# TSAL.net
KiCad netlist of a schematic drawn in Altium Designer
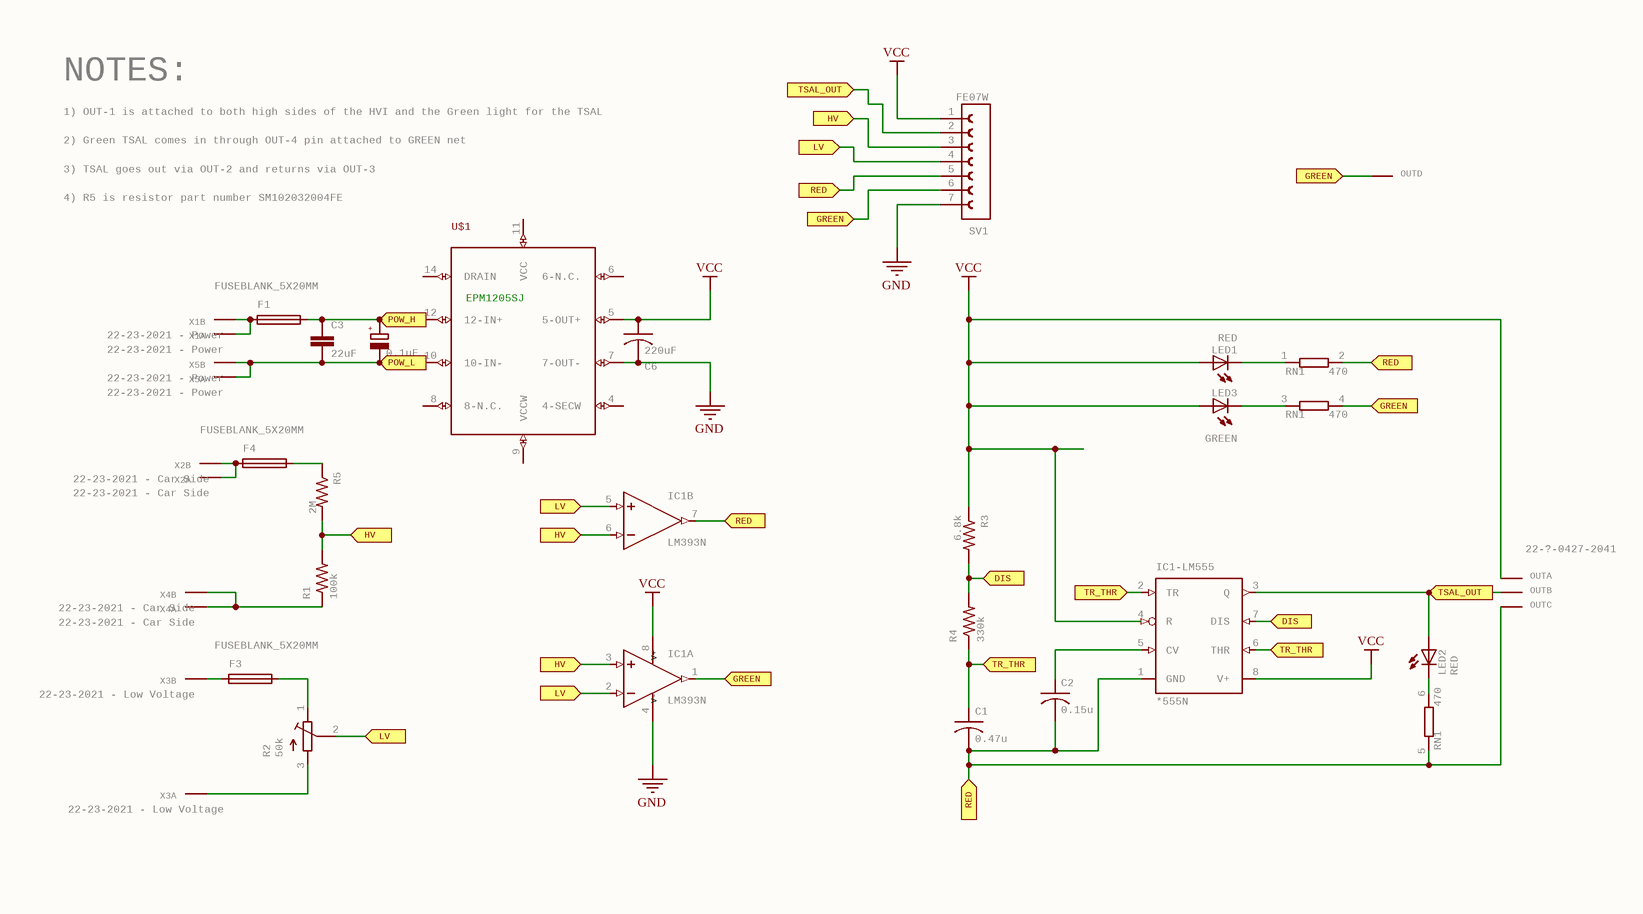
[diagram p0: TSAL.SchDoc]

(export (version "E")
  (design (tool "Eeschema 10.0.6"))
  (components
    (comp (ref "C1")
      (value "0.47u")
      (footprint "C050-075X075")
      (description "CAPACITOR, American symbol")
      (libsource (lib "rcl") (part "C-US050-075X075"))
    )
    (comp (ref "C2")
      (value "0.15u")
      (footprint "C050-075X075")
      (description "CAPACITOR, American symbol")
      (libsource (lib "rcl") (part "C-US050-075X075"))
    )
    (comp (ref "C3")
      (value "22uF")
      (footprint "C150-091X182")
      (description "CAPACITOR, European symbol")
      (libsource (lib "rcl") (part "C-EU150-091X182"))
    )
    (comp (ref "C5")
      (value "0.1uF")
      (footprint "E7,5-16")
      (description "POLARIZED CAPACITOR, European symbol")
      (fields (field (name "+") "+"))
      (libsource (lib "rcl") (part "CPOL-EUE7.5-16"))
    )
    (comp (ref "C6")
      (value "220uF")
      (footprint "C050-055X075")
      (description "CAPACITOR, American symbol")
      (libsource (lib "rcl") (part "C-US050-055X075"))
    )
    (comp (ref "F1")
      (value "FUSEBLANK_5X20MM")
      (footprint "FUSE_HOLDER_5X20MM")
      (description "Fuse")
      (fields (field (name "MF") "MF") (field (name "MPN") "MPN"))
      (libsource (lib "fuse") (part "FUSEBLANK_5X20MM"))
    )
    (comp (ref "F3")
      (value "FUSEBLANK_5X20MM")
      (footprint "FUSE_HOLDER_5X20MM")
      (description "Fuse")
      (fields (field (name "MF") "MF") (field (name "MPN") "MPN"))
      (libsource (lib "fuse") (part "FUSEBLANK_5X20MM"))
    )
    (comp (ref "F4")
      (value "FUSEBLANK_5X20MM")
      (footprint "FUSE_HOLDER_5X20MM")
      (description "Fuse")
      (fields (field (name "MF") "MF") (field (name "MPN") "MPN"))
      (libsource (lib "fuse") (part "FUSEBLANK_5X20MM"))
    )
    (comp (ref "IC1")
      (value "LM393N")
      (footprint "DIL08")
      (description "COMPARATOR")
      (fields (field (name "V+") "V+") (field (name "V-") "V-"))
      (libsource (lib "linear") (part "LM393N"))
    )
    (comp (ref "IC1-LM555")
      (value "*555N")
      (footprint "DIL08")
      (description "TIMER")
      (libsource (lib "linear") (part "*555N"))
    )
    (comp (ref "LED1") (value "RED") (footprint "LED3MM") (libsource (lib "led") (part "LED3MM")))
    (comp (ref "LED2") (value "RED") (footprint "LED3MM") (libsource (lib "led") (part "LED3MM")))
    (comp (ref "LED3") (value "GREEN") (footprint "LED3MM") (libsource (lib "led") (part "LED3MM")))
    (comp (ref "OUT")
      (value "22-?-0427-2041")
      (footprint "6410-04")
      (description "CONNECTOR   wire to board 2.54 mm (.1 inch) pitch header")
      (fields (field (name "MF") "MOLEX") (field (name "MPN") "MPN"))
      (libsource (lib "con-molex") (part "22-?-0427-2041"))
    )
    (comp (ref "R1")
      (value "100k")
      (footprint "0207/10")
      (description "RESISTOR, American symbol")
      (libsource (lib "resistor") (part "R-US_0207/10"))
    )
    (comp (ref "R2")
      (value "50k")
      (footprint "RTRIM3006P")
      (description "Trimm resistor")
      (libsource (lib "resistor") (part "R-TRIMM3006P"))
    )
    (comp (ref "R3")
      (value "6.8k")
      (footprint "0309/12")
      (description "RESISTOR, American symbol")
      (libsource (lib "resistor") (part "R-US_0309/12"))
    )
    (comp (ref "R4")
      (value "330k")
      (footprint "0309/12")
      (description "RESISTOR, American symbol")
      (libsource (lib "resistor") (part "R-US_0309/12"))
    )
    (comp (ref "R5")
      (value "2M")
      (footprint "0207/10")
      (description "RESISTOR, American symbol")
      (libsource (lib "resistor") (part "R-US_0207/10"))
    )
    (comp (ref "RN1")
      (value "470")
      (footprint "SIL6")
      (description "SIL RESISTOR")
      (fields (field (name "PART") "RN1") (field (name "MF") "MF") (field (name "MPN") "MPN"))
      (libsource (lib "resistor-sil") (part "E3RP"))
    )
    (comp (ref "SV1")
      (value "FE07W")
      (footprint "FE07W")
      (description "FEMALE HEADER")
      (fields (field (name "MF") "MF") (field (name "MPN") "MPN") (field (name "LIBRARYNAME") "con-lsta"))
      (libsource (lib "con-lsta") (part "FE07W"))
    )
    (comp (ref "U$1")
      (value "EPM1205SJ")
      (footprint "EPM1205SJ")
      (libsource (lib "DC-DC Converter") (part "EPM1205SJ"))
    )
    (comp (ref "X1")
      (value "22-23-2021 - Power")
      (footprint "22-23-2021")
      (description ".100\" (2.54mm) Center Header - 2 Pin")
      (fields (field (name "MF") "MOLEX") (field (name "MPN") "22-23-2021"))
      (libsource (lib "con-molex") (part "22-23-2021"))
    )
    (comp (ref "X2")
      (value "22-23-2021 - Car Side")
      (footprint "22-23-2021")
      (description ".100\" (2.54mm) Center Header - 2 Pin")
      (fields (field (name "MF") "MOLEX") (field (name "MPN") "22-23-2021"))
      (libsource (lib "con-molex") (part "22-23-2021"))
    )
    (comp (ref "X3")
      (value "22-23-2021 - Low Voltage")
      (footprint "22-23-2021")
      (description ".100\" (2.54mm) Center Header - 2 Pin")
      (fields (field (name "MF") "MOLEX") (field (name "MPN") "22-23-2021"))
      (libsource (lib "con-molex") (part "22-23-2021"))
    )
    (comp (ref "X4")
      (value "22-23-2021 - Car Side")
      (footprint "22-23-2021")
      (description ".100\" (2.54mm) Center Header - 2 Pin")
      (fields (field (name "MF") "MOLEX") (field (name "MPN") "22-23-2021"))
      (libsource (lib "con-molex") (part "22-23-2021"))
    )
    (comp (ref "X5")
      (value "22-23-2021 - Power")
      (footprint "22-23-2021")
      (description ".100\" (2.54mm) Center Header - 2 Pin")
      (fields (field (name "MF") "MOLEX") (field (name "MPN") "22-23-2021"))
      (libsource (lib "con-molex") (part "22-23-2021"))
    )
  )
  (nets
    (net (code "1") (name "/DIS") (class "Default")
      (node (ref "IC1-LM555") (pin "7") (pinfunction "DIS_7") (pintype "input"))
      (node (ref "R3") (pin "2") (pinfunction "2_2") (pintype "passive"))
      (node (ref "R4") (pin "2") (pinfunction "2_2") (pintype "passive"))
    )
    (net (code "2") (name "/GREEN") (class "Default")
      (node (ref "IC1") (pin "1") (pinfunction "OUT_1") (pintype "output"))
      (node (ref "OUT") (pin "4") (pinfunction "S_4") (pintype "passive"))
      (node (ref "RN1") (pin "4") (pinfunction "2_4") (pintype "passive"))
      (node (ref "SV1") (pin "6") (pinfunction "6_6") (pintype "passive"))
    )
    (net (code "3") (name "/HV") (class "Default")
      (node (ref "IC1") (pin "3") (pinfunction "+IN_3") (pintype "input"))
      (node (ref "IC1") (pin "6") (pinfunction "-IN_6") (pintype "input"))
      (node (ref "R1") (pin "2") (pinfunction "2_2") (pintype "passive"))
      (node (ref "R5") (pin "2") (pinfunction "2_2") (pintype "passive"))
      (node (ref "SV1") (pin "3") (pinfunction "3_3") (pintype "passive"))
    )
    (net (code "4") (name "/LV") (class "Default")
      (node (ref "IC1") (pin "2") (pinfunction "-IN_2") (pintype "input"))
      (node (ref "IC1") (pin "5") (pinfunction "+IN_5") (pintype "input"))
      (node (ref "R2") (pin "2") (pinfunction "S_2") (pintype "passive"))
      (node (ref "SV1") (pin "4") (pinfunction "4_4") (pintype "passive"))
    )
    (net (code "5") (name "/POW_H") (class "Default")
      (node (ref "C3") (pin "1") (pinfunction "1_1") (pintype "passive"))
      (node (ref "C5") (pin "+") (pinfunction "+_+") (pintype "passive"))
      (node (ref "F1") (pin "2") (pinfunction "2_2") (pintype "passive"))
      (node (ref "U$1") (pin "12") (pinfunction "12-IN+_12") (pintype "bidirectional"))
    )
    (net (code "6") (name "/POW_L") (class "Default")
      (node (ref "C3") (pin "2") (pinfunction "2_2") (pintype "passive"))
      (node (ref "C5") (pin "-") (pinfunction "-_-") (pintype "passive"))
      (node (ref "U$1") (pin "10") (pinfunction "10-IN-_10") (pintype "bidirectional"))
      (node (ref "X5") (pin "1") (pinfunction "S_1") (pintype "passive"))
      (node (ref "X5") (pin "2") (pinfunction "S_2") (pintype "passive"))
    )
    (net (code "7") (name "/RED") (class "Default")
      (node (ref "C1") (pin "2") (pinfunction "2_2") (pintype "passive"))
      (node (ref "C2") (pin "2") (pinfunction "2_2") (pintype "passive"))
      (node (ref "IC1") (pin "7") (pinfunction "OUT_7") (pintype "output"))
      (node (ref "IC1-LM555") (pin "1") (pinfunction "GND_1") (pintype "power_in"))
      (node (ref "OUT") (pin "3") (pinfunction "S_3") (pintype "passive"))
      (node (ref "RN1") (pin "2") (pinfunction "2_2") (pintype "passive"))
      (node (ref "RN1") (pin "5") (pinfunction "1_5") (pintype "passive"))
      (node (ref "SV1") (pin "5") (pinfunction "5_5") (pintype "passive"))
    )
    (net (code "8") (name "/TR_THR") (class "Default")
      (node (ref "C1") (pin "1") (pinfunction "1_1") (pintype "passive"))
      (node (ref "IC1-LM555") (pin "2") (pinfunction "TR_2") (pintype "input"))
      (node (ref "IC1-LM555") (pin "6") (pinfunction "THR_6") (pintype "input"))
      (node (ref "R4") (pin "1") (pinfunction "1_1") (pintype "passive"))
    )
    (net (code "9") (name "/TSAL_OUT") (class "Default")
      (node (ref "IC1-LM555") (pin "3") (pinfunction "Q_3") (pintype "output"))
      (node (ref "LED2") (pin "A") (pinfunction "A_A") (pintype "passive"))
      (node (ref "OUT") (pin "2") (pinfunction "S_2") (pintype "passive"))
      (node (ref "SV1") (pin "2") (pinfunction "2_2") (pintype "passive"))
    )
    (net (code "10") (name "GND") (class "Default")
      (node (ref "C6") (pin "2") (pinfunction "2_2") (pintype "passive"))
      (node (ref "IC1") (pin "4") (pinfunction "V-_4") (pintype "power_in"))
      (node (ref "SV1") (pin "7") (pinfunction "7_7") (pintype "passive"))
      (node (ref "U$1") (pin "7") (pinfunction "7-OUT-_7") (pintype "bidirectional"))
    )
    (net (code "11") (name "Net-(F4-Pad2)") (class "Default")
      (node (ref "F4") (pin "2") (pinfunction "2_2") (pintype "passive"))
      (node (ref "R5") (pin "1") (pinfunction "1_1") (pintype "passive"))
    )
    (net (code "12") (name "Net-(IC1-LM555-CV)") (class "Default")
      (node (ref "C2") (pin "1") (pinfunction "1_1") (pintype "passive"))
      (node (ref "IC1-LM555") (pin "5") (pinfunction "CV_5") (pintype "input"))
    )
    (net (code "13") (name "Net-(LED1-C)") (class "Default")
      (node (ref "LED1") (pin "K") (pinfunction "C_K") (pintype "passive"))
      (node (ref "RN1") (pin "1") (pinfunction "1_1") (pintype "passive"))
    )
    (net (code "14") (name "Net-(LED2-C)") (class "Default")
      (node (ref "LED2") (pin "K") (pinfunction "C_K") (pintype "passive"))
      (node (ref "RN1") (pin "6") (pinfunction "2_6") (pintype "passive"))
    )
    (net (code "15") (name "Net-(LED3-C)") (class "Default")
      (node (ref "LED3") (pin "K") (pinfunction "C_K") (pintype "passive"))
      (node (ref "RN1") (pin "3") (pinfunction "1_3") (pintype "passive"))
    )
    (net (code "16") (name "Net-(R2-A)") (class "Default")
      (node (ref "R2") (pin "3") (pinfunction "A_3") (pintype "passive"))
      (node (ref "X3") (pin "1") (pinfunction "S_1") (pintype "passive"))
    )
    (net (code "17") (name "Net-(R2-E)") (class "Default")
      (node (ref "F3") (pin "2") (pinfunction "2_2") (pintype "passive"))
      (node (ref "R2") (pin "1") (pinfunction "E_1") (pintype "passive"))
    )
    (net (code "18") (name "Net-(X1A-S)") (class "Default")
      (node (ref "F1") (pin "1") (pinfunction "1_1") (pintype "passive"))
      (node (ref "X1") (pin "1") (pinfunction "S_1") (pintype "passive"))
      (node (ref "X1") (pin "2") (pinfunction "S_2") (pintype "passive"))
    )
    (net (code "19") (name "Net-(X2A-S)") (class "Default")
      (node (ref "F4") (pin "1") (pinfunction "1_1") (pintype "passive"))
      (node (ref "X2") (pin "1") (pinfunction "S_1") (pintype "passive"))
      (node (ref "X2") (pin "2") (pinfunction "S_2") (pintype "passive"))
    )
    (net (code "20") (name "Net-(X3B-S)") (class "Default")
      (node (ref "F3") (pin "1") (pinfunction "1_1") (pintype "passive"))
      (node (ref "X3") (pin "2") (pinfunction "S_2") (pintype "passive"))
    )
    (net (code "21") (name "Net-(X4A-S)") (class "Default")
      (node (ref "R1") (pin "1") (pinfunction "1_1") (pintype "passive"))
      (node (ref "X4") (pin "1") (pinfunction "S_1") (pintype "passive"))
      (node (ref "X4") (pin "2") (pinfunction "S_2") (pintype "passive"))
    )
    (net (code "22") (name "VCC") (class "Default")
      (node (ref "C6") (pin "1") (pinfunction "1_1") (pintype "passive"))
      (node (ref "IC1") (pin "8") (pinfunction "V+_8") (pintype "power_in"))
      (node (ref "IC1-LM555") (pin "4") (pinfunction "R_4") (pintype "input"))
      (node (ref "IC1-LM555") (pin "8") (pinfunction "V+_8") (pintype "power_in"))
      (node (ref "LED1") (pin "A") (pinfunction "A_A") (pintype "passive"))
      (node (ref "LED3") (pin "A") (pinfunction "A_A") (pintype "passive"))
      (node (ref "OUT") (pin "1") (pinfunction "S_1") (pintype "passive"))
      (node (ref "R3") (pin "1") (pinfunction "1_1") (pintype "passive"))
      (node (ref "SV1") (pin "1") (pinfunction "1_1") (pintype "passive"))
      (node (ref "U$1") (pin "5") (pinfunction "5-OUT+_5") (pintype "bidirectional"))
    )
    (net (code "23") (name "unconnected-(U$1-4-SECW-Pad4)") (class "Default")
      (node (ref "U$1") (pin "4") (pinfunction "4-SECW_4") (pintype "bidirectional"))
    )
    (net (code "24") (name "unconnected-(U$1-6-N.C.-Pad6)") (class "Default")
      (node (ref "U$1") (pin "6") (pinfunction "6-N.C._6") (pintype "bidirectional"))
    )
    (net (code "25") (name "unconnected-(U$1-8-N.C.-Pad8)") (class "Default")
      (node (ref "U$1") (pin "8") (pinfunction "8-N.C._8") (pintype "bidirectional"))
    )
    (net (code "26") (name "unconnected-(U$1-DRAIN-Pad14)") (class "Default")
      (node (ref "U$1") (pin "14") (pinfunction "DRAIN_14") (pintype "bidirectional"))
    )
    (net (code "27") (name "unconnected-(U$1-VCC-Pad11)") (class "Default")
      (node (ref "U$1") (pin "11") (pinfunction "VCC_11") (pintype "bidirectional"))
    )
    (net (code "28") (name "unconnected-(U$1-VCCW-Pad9)") (class "Default")
      (node (ref "U$1") (pin "9") (pinfunction "VCCW_9") (pintype "bidirectional"))
    )
  )
)
